# bt.net
KiCad netlist of a schematic drawn in EAGLE
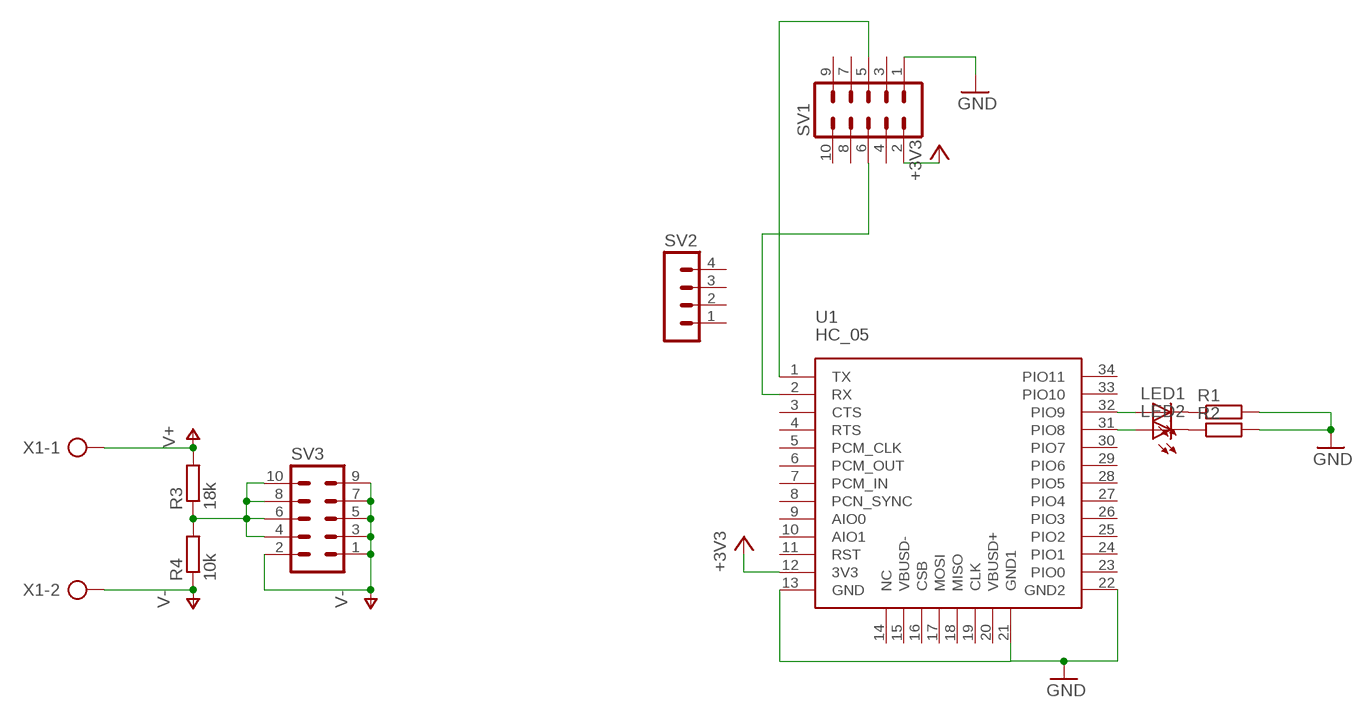
[diagram p0: schematic, sheet 1]

(export (version "E")
  (design (tool "Eeschema 10.0.6"))
  (components
    (comp (ref "LED1")
      (value "LED3MM")
      (footprint "eagle-import:LED3MM")
      (libsource (lib "eagle-import") (part "LED3MM"))
    )
    (comp (ref "LED2")
      (value "LED3MM")
      (footprint "eagle-import:LED3MM")
      (libsource (lib "eagle-import") (part "LED3MM"))
    )
    (comp (ref "R1")
      (value "R-EU_R0805")
      (footprint "eagle-import:R0805")
      (libsource (lib "eagle-import") (part "R-EU_R0805"))
    )
    (comp (ref "R2")
      (value "R-EU_R0805")
      (footprint "eagle-import:R0805")
      (libsource (lib "eagle-import") (part "R-EU_R0805"))
    )
    (comp (ref "R3")
      (value "18k")
      (footprint "eagle-import:R0805")
      (libsource (lib "eagle-import") (part "R-EU_R0805"))
    )
    (comp (ref "R4")
      (value "10k")
      (footprint "eagle-import:R0805")
      (libsource (lib "eagle-import") (part "R-EU_R0805"))
    )
    (comp (ref "SV1")
      (value "ML10")
      (footprint "eagle-import:ML10")
      (libsource (lib "eagle-import") (part "ML10"))
    )
    (comp (ref "SV2")
      (value "MA04-1")
      (footprint "eagle-import:MA04-1")
      (libsource (lib "eagle-import") (part "MA04-1"))
    )
    (comp (ref "SV3")
      (value "ML10")
      (footprint "eagle-import:ML10")
      (libsource (lib "eagle-import") (part "ML10"))
    )
    (comp (ref "U1")
      (value "HC_05")
      (footprint "eagle-import:BLUETOOTH_SMD")
      (libsource (lib "eagle-import") (part "HC_05"))
    )
    (comp (ref "X1")
      (value "AK500/2")
      (footprint "eagle-import:AK500_2")
      (libsource (lib "eagle-import") (part "AK500/2"))
    )
  )
  (nets
    (net (code "1") (name "+3V3") (class "Default")
      (node (ref "SV1") (pin "2") (pinfunction "2_2") (pintype "passive"))
      (node (ref "U1") (pin "12") (pinfunction "3V3_12") (pintype "bidirectional"))
    )
    (net (code "2") (name "GND") (class "Default")
      (node (ref "R1") (pin "2") (pinfunction "2_2") (pintype "passive"))
      (node (ref "R2") (pin "2") (pinfunction "2_2") (pintype "passive"))
      (node (ref "SV1") (pin "1") (pinfunction "1_1") (pintype "passive"))
      (node (ref "U1") (pin "13") (pinfunction "GND_13") (pintype "bidirectional"))
      (node (ref "U1") (pin "21") (pinfunction "GND1_21") (pintype "bidirectional"))
      (node (ref "U1") (pin "22") (pinfunction "GND2_22") (pintype "bidirectional"))
    )
    (net (code "3") (name "Net-(LED1-C)") (class "Default")
      (node (ref "LED1") (pin "K") (pinfunction "C_K") (pintype "passive"))
      (node (ref "R1") (pin "1") (pinfunction "1_1") (pintype "passive"))
    )
    (net (code "4") (name "Net-(LED2-C)") (class "Default")
      (node (ref "LED2") (pin "K") (pinfunction "C_K") (pintype "passive"))
      (node (ref "R2") (pin "1") (pinfunction "1_1") (pintype "passive"))
    )
    (net (code "5") (name "Net-(R3-Pad1)") (class "Default")
      (node (ref "R3") (pin "1") (pinfunction "1_1") (pintype "passive"))
      (node (ref "R4") (pin "2") (pinfunction "2_2") (pintype "passive"))
      (node (ref "SV3") (pin "10") (pinfunction "10_10") (pintype "passive"))
      (node (ref "SV3") (pin "4") (pinfunction "4_4") (pintype "passive"))
      (node (ref "SV3") (pin "6") (pinfunction "6_6") (pintype "passive"))
      (node (ref "SV3") (pin "8") (pinfunction "8_8") (pintype "passive"))
    )
    (net (code "6") (name "Net-(U1-PIO8)") (class "Default")
      (node (ref "LED2") (pin "A") (pinfunction "A_A") (pintype "passive"))
      (node (ref "U1") (pin "31") (pinfunction "PIO8_31") (pintype "bidirectional"))
    )
    (net (code "7") (name "Net-(U1-PIO9)") (class "Default")
      (node (ref "LED1") (pin "A") (pinfunction "A_A") (pintype "passive"))
      (node (ref "U1") (pin "32") (pinfunction "PIO9_32") (pintype "bidirectional"))
    )
    (net (code "8") (name "Net-(U1-RX)") (class "Default")
      (node (ref "SV1") (pin "6") (pinfunction "6_6") (pintype "passive"))
      (node (ref "U1") (pin "2") (pinfunction "RX_2") (pintype "bidirectional"))
    )
    (net (code "9") (name "Net-(U1-TX)") (class "Default")
      (node (ref "SV1") (pin "5") (pinfunction "5_5") (pintype "passive"))
      (node (ref "U1") (pin "1") (pinfunction "TX_1") (pintype "bidirectional"))
    )
    (net (code "10") (name "V+") (class "Default")
      (node (ref "R3") (pin "2") (pinfunction "2_2") (pintype "passive"))
      (node (ref "X1") (pin "1") (pinfunction "KL_1") (pintype "passive"))
    )
    (net (code "11") (name "V-") (class "Default")
      (node (ref "R4") (pin "1") (pinfunction "1_1") (pintype "passive"))
      (node (ref "SV3") (pin "1") (pinfunction "1_1") (pintype "passive"))
      (node (ref "SV3") (pin "2") (pinfunction "2_2") (pintype "passive"))
      (node (ref "SV3") (pin "3") (pinfunction "3_3") (pintype "passive"))
      (node (ref "SV3") (pin "5") (pinfunction "5_5") (pintype "passive"))
      (node (ref "SV3") (pin "7") (pinfunction "7_7") (pintype "passive"))
      (node (ref "SV3") (pin "9") (pinfunction "9_9") (pintype "passive"))
      (node (ref "X1") (pin "2") (pinfunction "KL_2") (pintype "passive"))
    )
    (net (code "12") (name "unconnected-(SV1-Pad3)") (class "Default")
      (node (ref "SV1") (pin "3") (pinfunction "3_3") (pintype "passive"))
    )
    (net (code "13") (name "unconnected-(SV1-Pad4)") (class "Default")
      (node (ref "SV1") (pin "4") (pinfunction "4_4") (pintype "passive"))
    )
    (net (code "14") (name "unconnected-(SV1-Pad7)") (class "Default")
      (node (ref "SV1") (pin "7") (pinfunction "7_7") (pintype "passive"))
    )
    (net (code "15") (name "unconnected-(SV1-Pad8)") (class "Default")
      (node (ref "SV1") (pin "8") (pinfunction "8_8") (pintype "passive"))
    )
    (net (code "16") (name "unconnected-(SV1-Pad9)") (class "Default")
      (node (ref "SV1") (pin "9") (pinfunction "9_9") (pintype "passive"))
    )
    (net (code "17") (name "unconnected-(SV1-Pad10)") (class "Default")
      (node (ref "SV1") (pin "10") (pinfunction "10_10") (pintype "passive"))
    )
    (net (code "18") (name "unconnected-(SV2-Pad1)") (class "Default")
      (node (ref "SV2") (pin "1") (pinfunction "1_1") (pintype "passive"))
    )
    (net (code "19") (name "unconnected-(SV2-Pad2)") (class "Default")
      (node (ref "SV2") (pin "2") (pinfunction "2_2") (pintype "passive"))
    )
    (net (code "20") (name "unconnected-(SV2-Pad3)") (class "Default")
      (node (ref "SV2") (pin "3") (pinfunction "3_3") (pintype "passive"))
    )
    (net (code "21") (name "unconnected-(SV2-Pad4)") (class "Default")
      (node (ref "SV2") (pin "4") (pinfunction "4_4") (pintype "passive"))
    )
    (net (code "22") (name "unconnected-(U1-AIO0-Pad9)") (class "Default")
      (node (ref "U1") (pin "9") (pinfunction "AIO0_9") (pintype "bidirectional"))
    )
    (net (code "23") (name "unconnected-(U1-AIO1-Pad10)") (class "Default")
      (node (ref "U1") (pin "10") (pinfunction "AIO1_10") (pintype "bidirectional"))
    )
    (net (code "24") (name "unconnected-(U1-CLK-Pad19)") (class "Default")
      (node (ref "U1") (pin "19") (pinfunction "CLK_19") (pintype "bidirectional"))
    )
    (net (code "25") (name "unconnected-(U1-CSB-Pad16)") (class "Default")
      (node (ref "U1") (pin "16") (pinfunction "CSB_16") (pintype "bidirectional"))
    )
    (net (code "26") (name "unconnected-(U1-CTS-Pad3)") (class "Default")
      (node (ref "U1") (pin "3") (pinfunction "CTS_3") (pintype "bidirectional"))
    )
    (net (code "27") (name "unconnected-(U1-MISO-Pad18)") (class "Default")
      (node (ref "U1") (pin "18") (pinfunction "MISO_18") (pintype "bidirectional"))
    )
    (net (code "28") (name "unconnected-(U1-MOSI-Pad17)") (class "Default")
      (node (ref "U1") (pin "17") (pinfunction "MOSI_17") (pintype "bidirectional"))
    )
    (net (code "29") (name "unconnected-(U1-NC-Pad14)") (class "Default")
      (node (ref "U1") (pin "14") (pinfunction "NC_14") (pintype "bidirectional"))
    )
    (net (code "30") (name "unconnected-(U1-PCM_CLK-Pad5)") (class "Default")
      (node (ref "U1") (pin "5") (pinfunction "PCM_CLK_5") (pintype "bidirectional"))
    )
    (net (code "31") (name "unconnected-(U1-PCM_IN-Pad7)") (class "Default")
      (node (ref "U1") (pin "7") (pinfunction "PCM_IN_7") (pintype "bidirectional"))
    )
    (net (code "32") (name "unconnected-(U1-PCM_OUT-Pad6)") (class "Default")
      (node (ref "U1") (pin "6") (pinfunction "PCM_OUT_6") (pintype "bidirectional"))
    )
    (net (code "33") (name "unconnected-(U1-PCN_SYNC-Pad8)") (class "Default")
      (node (ref "U1") (pin "8") (pinfunction "PCN_SYNC_8") (pintype "bidirectional"))
    )
    (net (code "34") (name "unconnected-(U1-PIO0-Pad23)") (class "Default")
      (node (ref "U1") (pin "23") (pinfunction "PIO0_23") (pintype "bidirectional"))
    )
    (net (code "35") (name "unconnected-(U1-PIO1-Pad24)") (class "Default")
      (node (ref "U1") (pin "24") (pinfunction "PIO1_24") (pintype "bidirectional"))
    )
    (net (code "36") (name "unconnected-(U1-PIO2-Pad25)") (class "Default")
      (node (ref "U1") (pin "25") (pinfunction "PIO2_25") (pintype "bidirectional"))
    )
    (net (code "37") (name "unconnected-(U1-PIO3-Pad26)") (class "Default")
      (node (ref "U1") (pin "26") (pinfunction "PIO3_26") (pintype "bidirectional"))
    )
    (net (code "38") (name "unconnected-(U1-PIO4-Pad27)") (class "Default")
      (node (ref "U1") (pin "27") (pinfunction "PIO4_27") (pintype "bidirectional"))
    )
    (net (code "39") (name "unconnected-(U1-PIO5-Pad28)") (class "Default")
      (node (ref "U1") (pin "28") (pinfunction "PIO5_28") (pintype "bidirectional"))
    )
    (net (code "40") (name "unconnected-(U1-PIO6-Pad29)") (class "Default")
      (node (ref "U1") (pin "29") (pinfunction "PIO6_29") (pintype "bidirectional"))
    )
    (net (code "41") (name "unconnected-(U1-PIO7-Pad30)") (class "Default")
      (node (ref "U1") (pin "30") (pinfunction "PIO7_30") (pintype "bidirectional"))
    )
    (net (code "42") (name "unconnected-(U1-PIO10-Pad33)") (class "Default")
      (node (ref "U1") (pin "33") (pinfunction "PIO10_33") (pintype "bidirectional"))
    )
    (net (code "43") (name "unconnected-(U1-PIO11-Pad34)") (class "Default")
      (node (ref "U1") (pin "34") (pinfunction "PIO11_34") (pintype "bidirectional"))
    )
    (net (code "44") (name "unconnected-(U1-RST-Pad11)") (class "Default")
      (node (ref "U1") (pin "11") (pinfunction "RST_11") (pintype "bidirectional"))
    )
    (net (code "45") (name "unconnected-(U1-RTS-Pad4)") (class "Default")
      (node (ref "U1") (pin "4") (pinfunction "RTS_4") (pintype "bidirectional"))
    )
    (net (code "46") (name "unconnected-(U1-VBUSD+-Pad20)") (class "Default")
      (node (ref "U1") (pin "20") (pinfunction "VBUSD+_20") (pintype "bidirectional"))
    )
    (net (code "47") (name "unconnected-(U1-VBUSD--Pad15)") (class "Default")
      (node (ref "U1") (pin "15") (pinfunction "VBUSD-_15") (pintype "bidirectional"))
    )
  )
)
